# pcb_telemetria.net
KiCad netlist of a schematic drawn in EAGLE
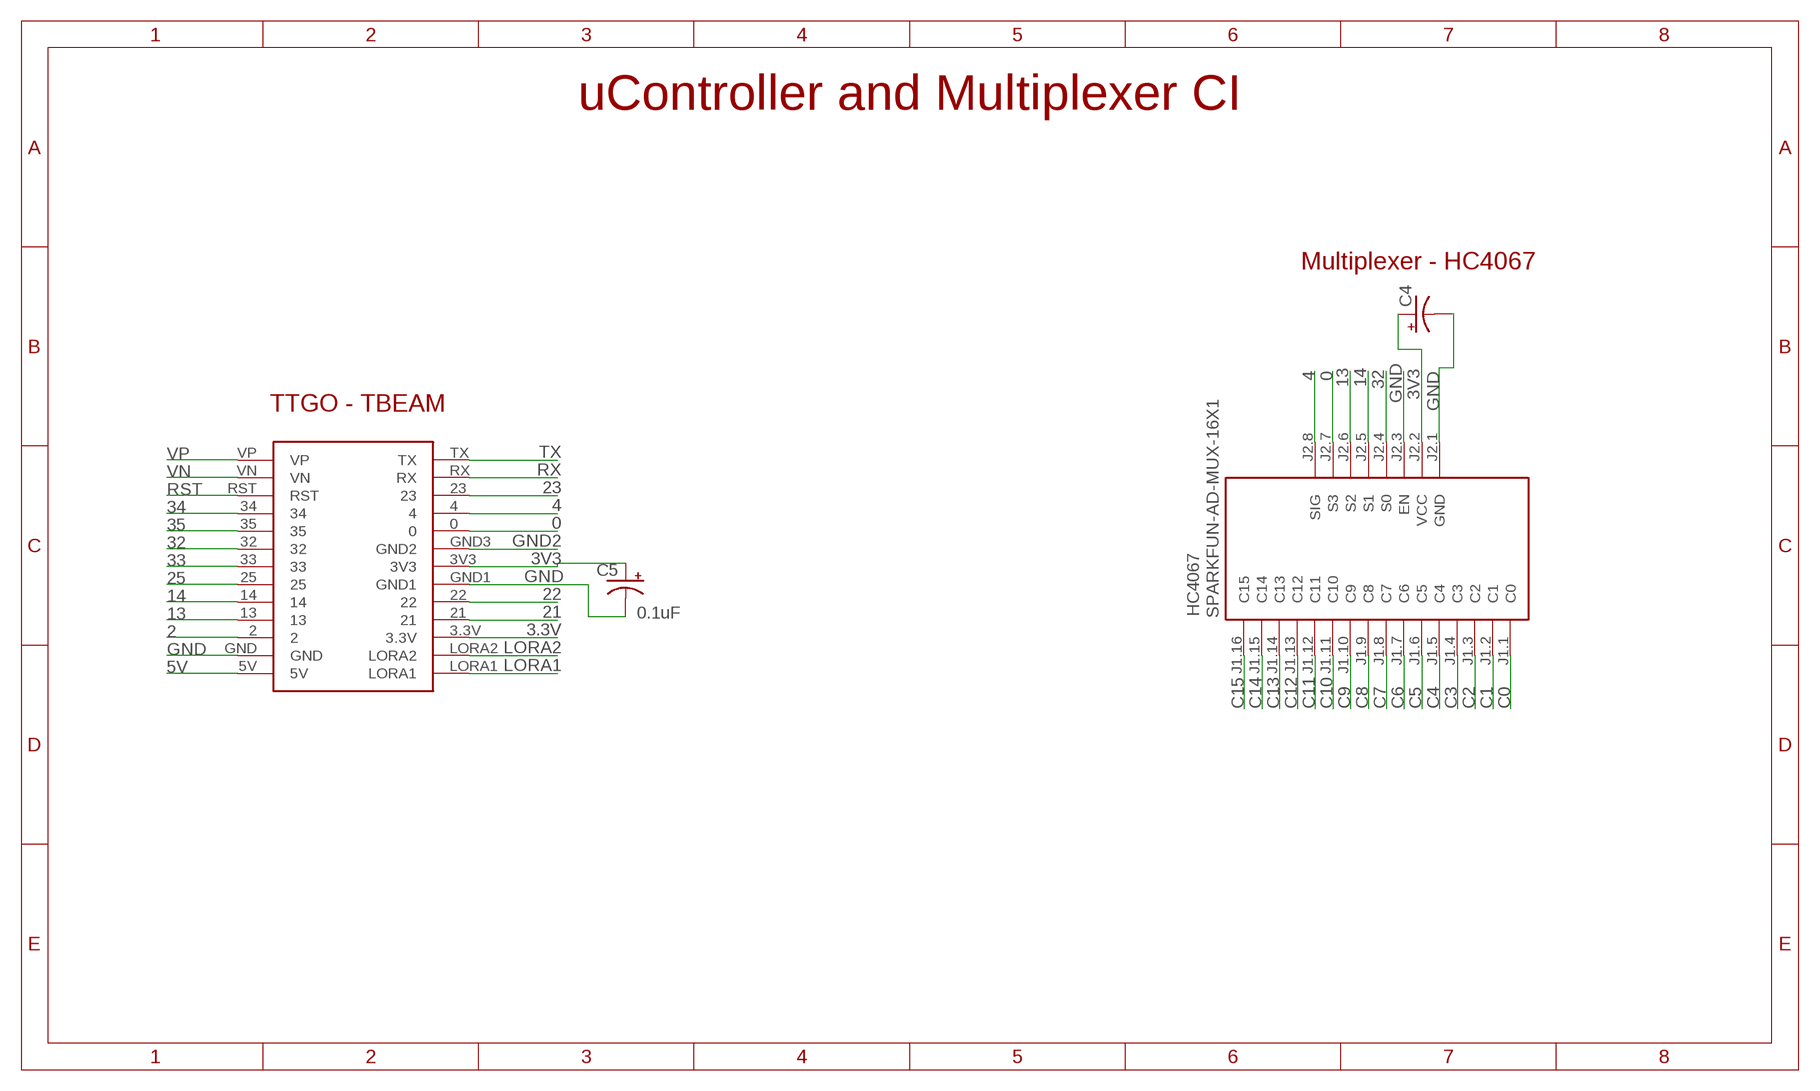
[diagram p0: schematic, sheet 1]
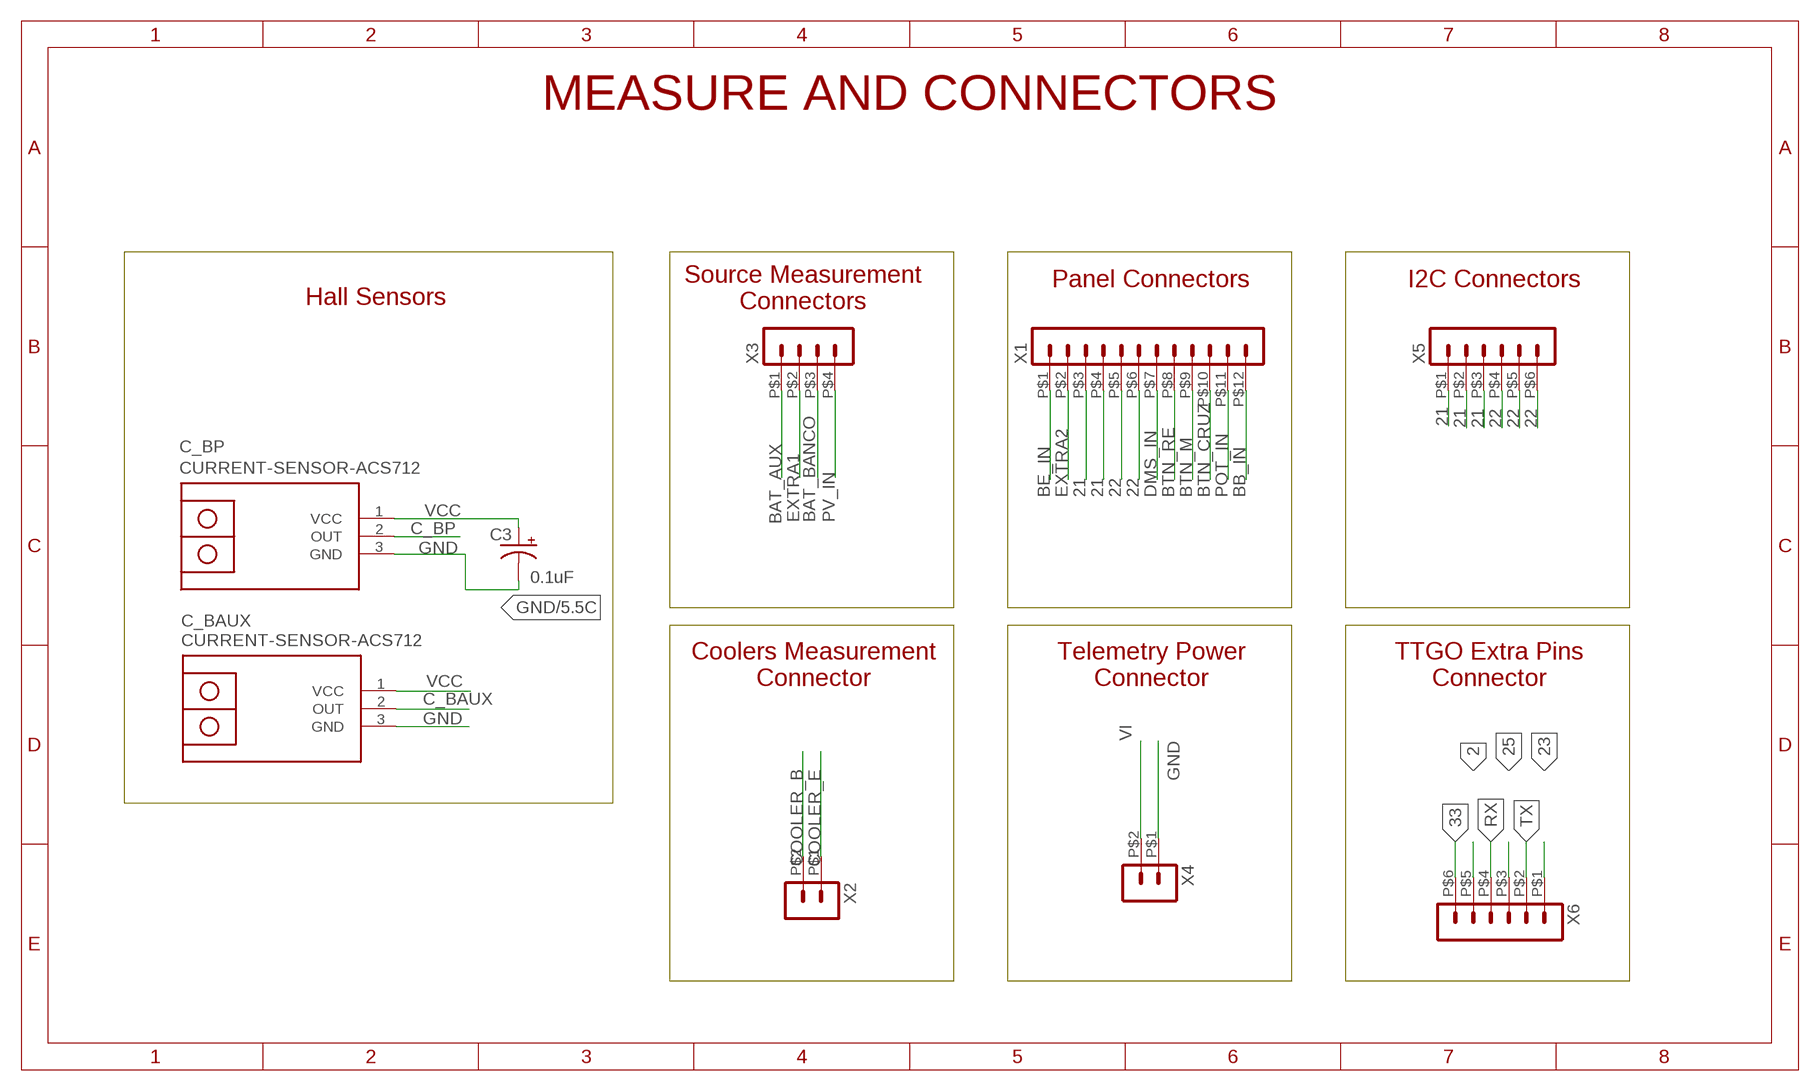
[diagram p1: schematic, sheet 2]
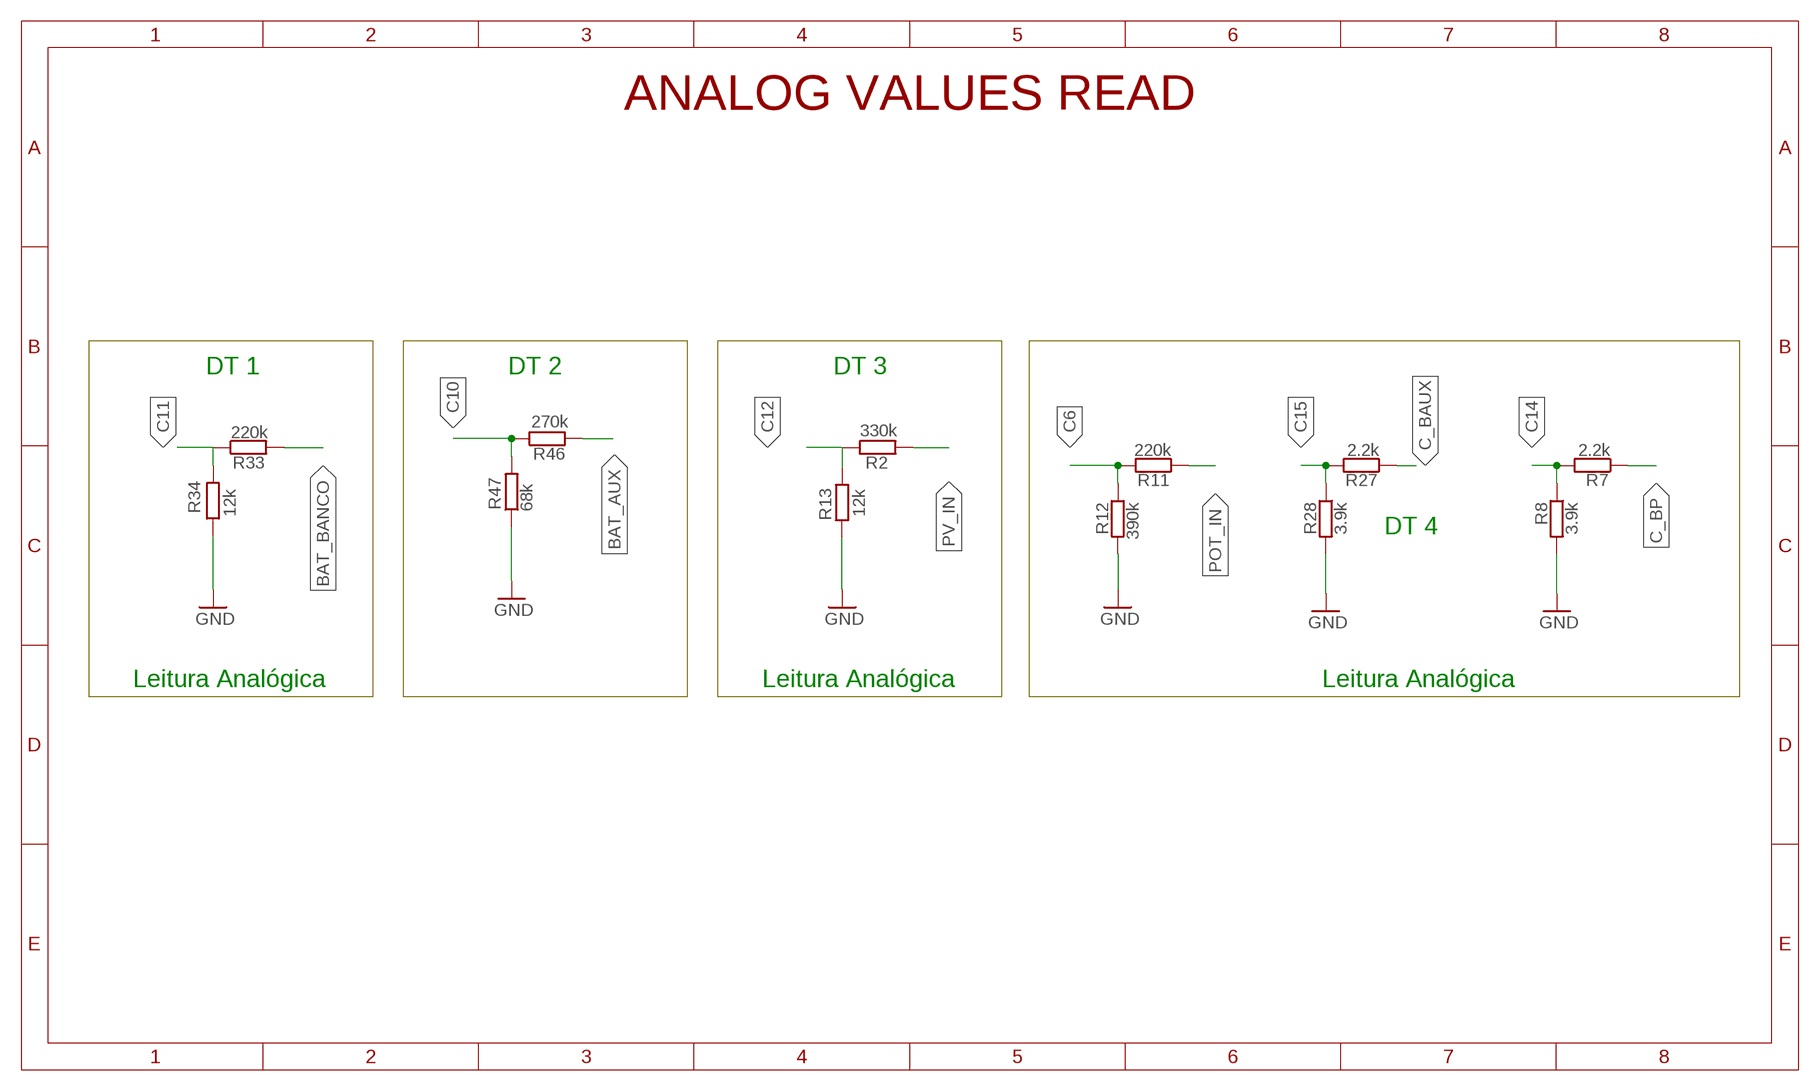
[diagram p2: schematic, sheet 3]
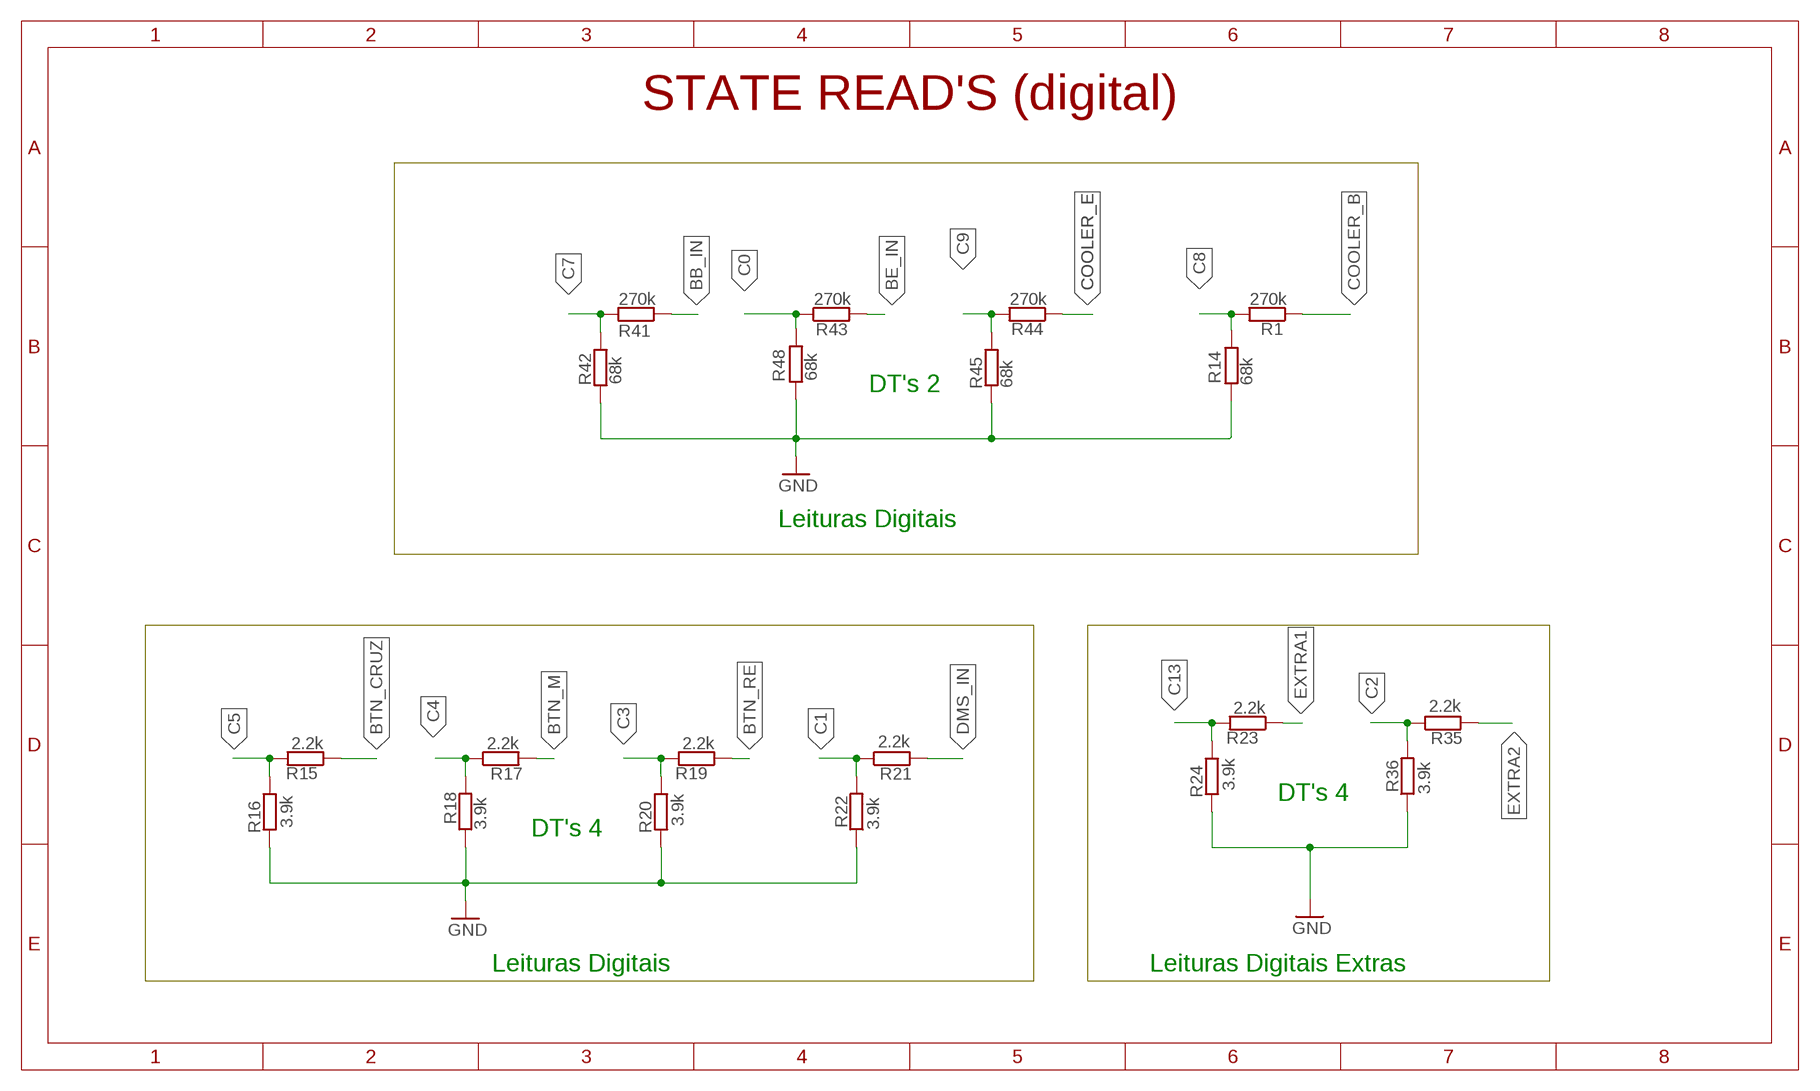
[diagram p3: schematic, sheet 4]
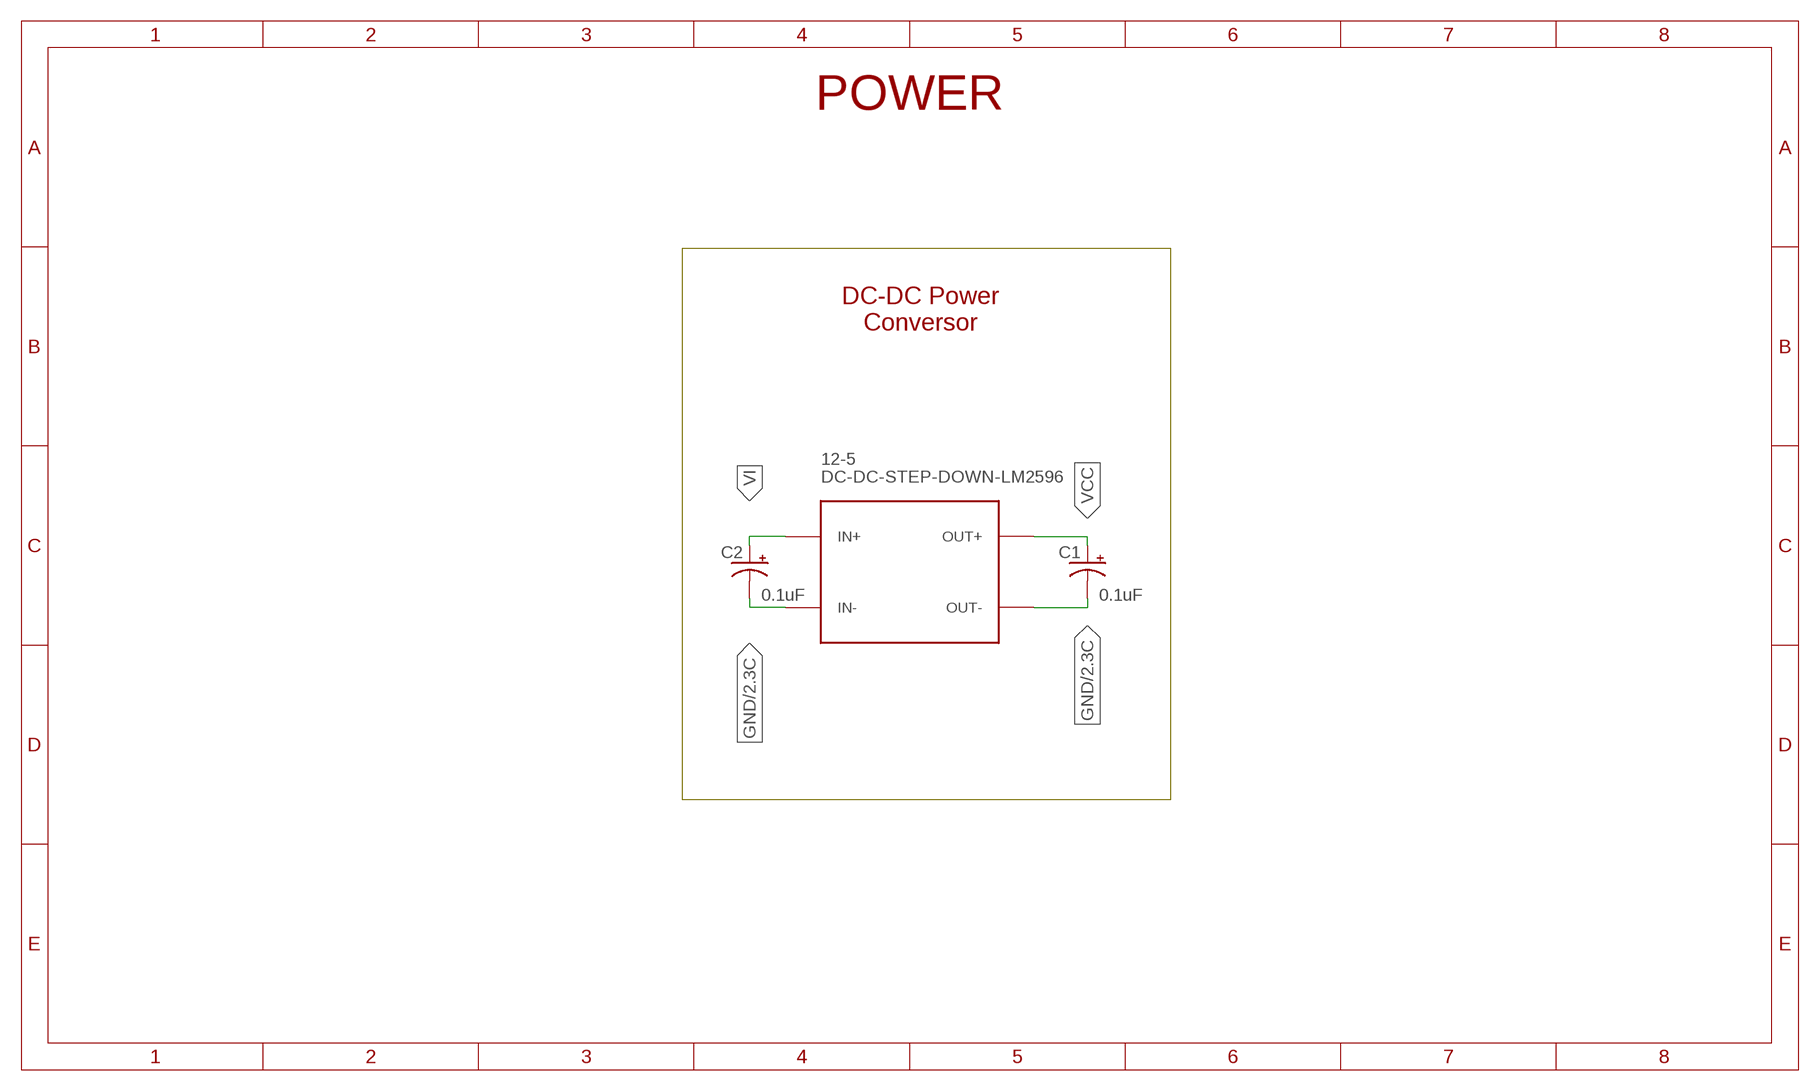
[diagram p4: schematic, sheet 5]

(export (version "E")
  (design (tool "Eeschema 10.0.6"))
  (components
    (comp (ref "C4")
      (value "CPOL-USE5-5")
      (footprint "eagle-import:E5-5")
      (libsource (lib "eagle-import") (part "CPOL-USE5-5"))
    )
    (comp (ref "C5")
      (value "0.1uF")
      (footprint "eagle-import:E5-5")
      (libsource (lib "eagle-import") (part "CPOL-USE5-5"))
    )
    (comp (ref "HC4067")
      (value "SPARKFUN-AD-MUX-16X1")
      (footprint "eagle-import:SPARKFUN-AD-MUX-16X1")
      (libsource (lib "eagle-import") (part "SPARKFUN-AD-MUX-16X1"))
    )
    (comp (ref "U$1")
      (value "TTGOBEAM")
      (footprint "eagle-import:TTGOBEAM")
      (libsource (lib "eagle-import") (part "TTGOBEAM"))
    )
    (comp (ref "R2")
      (value "330k")
      (footprint "eagle-import:0204_7")
      (libsource (lib "eagle-import") (part "R-EU_0204/7"))
    )
    (comp (ref "R7")
      (value "2.2k")
      (footprint "eagle-import:0204_7")
      (libsource (lib "eagle-import") (part "R-EU_0204/7"))
    )
    (comp (ref "R8")
      (value "3.9k")
      (footprint "eagle-import:0204_7")
      (libsource (lib "eagle-import") (part "R-EU_0204/7"))
    )
    (comp (ref "R11")
      (value "220k")
      (footprint "eagle-import:0204_7")
      (libsource (lib "eagle-import") (part "R-EU_0204/7"))
    )
    (comp (ref "R12")
      (value "390k")
      (footprint "eagle-import:0204_7")
      (libsource (lib "eagle-import") (part "R-EU_0204/7"))
    )
    (comp (ref "R13")
      (value "12k")
      (footprint "eagle-import:0204_7")
      (libsource (lib "eagle-import") (part "R-EU_0204/7"))
    )
    (comp (ref "R27")
      (value "2.2k")
      (footprint "eagle-import:0204_7")
      (libsource (lib "eagle-import") (part "R-EU_0204/7"))
    )
    (comp (ref "R28")
      (value "3.9k")
      (footprint "eagle-import:0204_7")
      (libsource (lib "eagle-import") (part "R-EU_0204/7"))
    )
    (comp (ref "R33")
      (value "220k")
      (footprint "eagle-import:0204_7")
      (libsource (lib "eagle-import") (part "R-EU_0204/7"))
    )
    (comp (ref "R34")
      (value "12k")
      (footprint "eagle-import:0204_7")
      (libsource (lib "eagle-import") (part "R-EU_0204/7"))
    )
    (comp (ref "R46")
      (value "270k")
      (footprint "eagle-import:0204_7")
      (libsource (lib "eagle-import") (part "R-EU_0204/7"))
    )
    (comp (ref "R47")
      (value "68k")
      (footprint "eagle-import:0204_7")
      (libsource (lib "eagle-import") (part "R-EU_0204/7"))
    )
    (comp (ref "12-5")
      (value "DC-DC-STEP-DOWN-LM2596")
      (footprint "eagle-import:DC-DC-STEP-DOWN-LM2596")
      (libsource (lib "eagle-import") (part "DC-DC-STEP-DOWN-LM2596"))
    )
    (comp (ref "C1")
      (value "0.1uF")
      (footprint "eagle-import:E5-5")
      (libsource (lib "eagle-import") (part "CPOL-USE5-5"))
    )
    (comp (ref "C2")
      (value "0.1uF")
      (footprint "eagle-import:E5-5")
      (libsource (lib "eagle-import") (part "CPOL-USE5-5"))
    )
    (comp (ref "C3")
      (value "0.1uF")
      (footprint "eagle-import:E5-5")
      (libsource (lib "eagle-import") (part "CPOL-USE5-5"))
    )
    (comp (ref "C_BAUX")
      (value "CURRENT-SENSOR-ACS712")
      (footprint "eagle-import:CURRENT-SENSOR-ACS712")
      (libsource (lib "eagle-import") (part "CURRENT-SENSOR-ACS712"))
    )
    (comp (ref "C_BP")
      (value "CURRENT-SENSOR-ACS712")
      (footprint "eagle-import:CURRENT-SENSOR-ACS712")
      (libsource (lib "eagle-import") (part "CURRENT-SENSOR-ACS712"))
    )
    (comp (ref "X1")
      (value "HEADER_POS12_43045-1212")
      (footprint "eagle-import:43045-1212")
      (libsource (lib "eagle-import") (part "HEADER_POS12_?43045-1212"))
    )
    (comp (ref "X2")
      (value "HEADER_POS2_43045-0212")
      (footprint "eagle-import:43045-0212")
      (libsource (lib "eagle-import") (part "HEADER_POS2_?43045-0212"))
    )
    (comp (ref "X3")
      (value "HEADER_POS4_43045-0412")
      (footprint "eagle-import:43045-0412")
      (libsource (lib "eagle-import") (part "HEADER_POS4_?43045-0412"))
    )
    (comp (ref "X4")
      (value "HEADER_POS2_43045-0212")
      (footprint "eagle-import:43045-0212")
      (libsource (lib "eagle-import") (part "HEADER_POS2_?43045-0212"))
    )
    (comp (ref "X5")
      (value "HEADER_POS6_43045-0612")
      (footprint "eagle-import:43045-0612")
      (libsource (lib "eagle-import") (part "HEADER_POS6_?43045-0612"))
    )
    (comp (ref "X6")
      (value "HEADER_POS6_43045-0612")
      (footprint "eagle-import:43045-0612")
      (libsource (lib "eagle-import") (part "HEADER_POS6_?43045-0612"))
    )
    (comp (ref "R1")
      (value "270k")
      (footprint "eagle-import:0204_7")
      (libsource (lib "eagle-import") (part "R-EU_0204/7"))
    )
    (comp (ref "R14")
      (value "68k")
      (footprint "eagle-import:0204_7")
      (libsource (lib "eagle-import") (part "R-EU_0204/7"))
    )
    (comp (ref "R15")
      (value "2.2k")
      (footprint "eagle-import:0204_7")
      (libsource (lib "eagle-import") (part "R-EU_0204/7"))
    )
    (comp (ref "R16")
      (value "3.9k")
      (footprint "eagle-import:0204_7")
      (libsource (lib "eagle-import") (part "R-EU_0204/7"))
    )
    (comp (ref "R17")
      (value "2.2k")
      (footprint "eagle-import:0204_7")
      (libsource (lib "eagle-import") (part "R-EU_0204/7"))
    )
    (comp (ref "R18")
      (value "3.9k")
      (footprint "eagle-import:0204_7")
      (libsource (lib "eagle-import") (part "R-EU_0204/7"))
    )
    (comp (ref "R19")
      (value "2.2k")
      (footprint "eagle-import:0204_7")
      (libsource (lib "eagle-import") (part "R-EU_0204/7"))
    )
    (comp (ref "R20")
      (value "3.9k")
      (footprint "eagle-import:0204_7")
      (libsource (lib "eagle-import") (part "R-EU_0204/7"))
    )
    (comp (ref "R21")
      (value "2.2k")
      (footprint "eagle-import:0204_7")
      (libsource (lib "eagle-import") (part "R-EU_0204/7"))
    )
    (comp (ref "R22")
      (value "3.9k")
      (footprint "eagle-import:0204_7")
      (libsource (lib "eagle-import") (part "R-EU_0204/7"))
    )
    (comp (ref "R23")
      (value "2.2k")
      (footprint "eagle-import:0204_7")
      (libsource (lib "eagle-import") (part "R-EU_0204/7"))
    )
    (comp (ref "R24")
      (value "3.9k")
      (footprint "eagle-import:0204_7")
      (libsource (lib "eagle-import") (part "R-EU_0204/7"))
    )
    (comp (ref "R35")
      (value "2.2k")
      (footprint "eagle-import:0204_7")
      (libsource (lib "eagle-import") (part "R-EU_0204/7"))
    )
    (comp (ref "R36")
      (value "3.9k")
      (footprint "eagle-import:0204_7")
      (libsource (lib "eagle-import") (part "R-EU_0204/7"))
    )
    (comp (ref "R41")
      (value "270k")
      (footprint "eagle-import:0204_7")
      (libsource (lib "eagle-import") (part "R-EU_0204/7"))
    )
    (comp (ref "R42")
      (value "68k")
      (footprint "eagle-import:0204_7")
      (libsource (lib "eagle-import") (part "R-EU_0204/7"))
    )
    (comp (ref "R43")
      (value "270k")
      (footprint "eagle-import:0204_7")
      (libsource (lib "eagle-import") (part "R-EU_0204/7"))
    )
    (comp (ref "R44")
      (value "270k")
      (footprint "eagle-import:0204_7")
      (libsource (lib "eagle-import") (part "R-EU_0204/7"))
    )
    (comp (ref "R45")
      (value "68k")
      (footprint "eagle-import:0204_7")
      (libsource (lib "eagle-import") (part "R-EU_0204/7"))
    )
    (comp (ref "R48")
      (value "68k")
      (footprint "eagle-import:0204_7")
      (libsource (lib "eagle-import") (part "R-EU_0204/7"))
    )
  )
  (nets
    (net (code "1") (name "0") (class "Default")
      (node (ref "HC4067") (pin "J2.7") (pinfunction "S3_J2.7") (pintype "bidirectional"))
      (node (ref "U$1") (pin "0") (pinfunction "0_0") (pintype "bidirectional"))
    )
    (net (code "2") (name "2") (class "Default")
      (node (ref "U$1") (pin "2") (pinfunction "2_2") (pintype "bidirectional"))
      (node (ref "X6") (pin "P$5") (pinfunction "5_P$5") (pintype "passive"))
    )
    (net (code "3") (name "3.3V") (class "Default")
      (node (ref "U$1") (pin "3.3V") (pinfunction "3.3V_3.3V") (pintype "bidirectional"))
    )
    (net (code "4") (name "3V3") (class "Default")
      (node (ref "C4") (pin "+") (pinfunction "+_+") (pintype "passive"))
      (node (ref "C5") (pin "+") (pinfunction "+_+") (pintype "passive"))
      (node (ref "HC4067") (pin "J2.2") (pinfunction "VCC_J2.2") (pintype "power_in"))
      (node (ref "U$1") (pin "3V3") (pinfunction "3V3_3V3") (pintype "bidirectional"))
    )
    (net (code "5") (name "4") (class "Default")
      (node (ref "HC4067") (pin "J2.8") (pinfunction "SIG_J2.8") (pintype "bidirectional"))
      (node (ref "U$1") (pin "4") (pinfunction "4_4") (pintype "bidirectional"))
    )
    (net (code "6") (name "5V") (class "Default")
      (node (ref "U$1") (pin "5V") (pinfunction "5V_5V") (pintype "bidirectional"))
    )
    (net (code "7") (name "13") (class "Default")
      (node (ref "HC4067") (pin "J2.6") (pinfunction "S2_J2.6") (pintype "bidirectional"))
      (node (ref "U$1") (pin "13") (pinfunction "13_13") (pintype "bidirectional"))
    )
    (net (code "8") (name "14") (class "Default")
      (node (ref "HC4067") (pin "J2.5") (pinfunction "S1_J2.5") (pintype "bidirectional"))
      (node (ref "U$1") (pin "14") (pinfunction "14_14") (pintype "bidirectional"))
    )
    (net (code "9") (name "21") (class "Default")
      (node (ref "U$1") (pin "21") (pinfunction "21_21") (pintype "bidirectional"))
      (node (ref "X1") (pin "P$3") (pinfunction "3_P$3") (pintype "passive"))
      (node (ref "X1") (pin "P$4") (pinfunction "4_P$4") (pintype "passive"))
      (node (ref "X5") (pin "P$1") (pinfunction "1_P$1") (pintype "passive"))
      (node (ref "X5") (pin "P$2") (pinfunction "2_P$2") (pintype "passive"))
      (node (ref "X5") (pin "P$3") (pinfunction "3_P$3") (pintype "passive"))
    )
    (net (code "10") (name "22") (class "Default")
      (node (ref "U$1") (pin "22") (pinfunction "22_22") (pintype "bidirectional"))
      (node (ref "X1") (pin "P$5") (pinfunction "5_P$5") (pintype "passive"))
      (node (ref "X1") (pin "P$6") (pinfunction "6_P$6") (pintype "passive"))
      (node (ref "X5") (pin "P$4") (pinfunction "4_P$4") (pintype "passive"))
      (node (ref "X5") (pin "P$5") (pinfunction "5_P$5") (pintype "passive"))
      (node (ref "X5") (pin "P$6") (pinfunction "6_P$6") (pintype "passive"))
    )
    (net (code "11") (name "23") (class "Default")
      (node (ref "U$1") (pin "23") (pinfunction "23_23") (pintype "bidirectional"))
      (node (ref "X6") (pin "P$1") (pinfunction "1_P$1") (pintype "passive"))
    )
    (net (code "12") (name "25") (class "Default")
      (node (ref "U$1") (pin "25") (pinfunction "25_25") (pintype "bidirectional"))
      (node (ref "X6") (pin "P$3") (pinfunction "3_P$3") (pintype "passive"))
    )
    (net (code "13") (name "32") (class "Default")
      (node (ref "HC4067") (pin "J2.4") (pinfunction "S0_J2.4") (pintype "bidirectional"))
      (node (ref "U$1") (pin "32") (pinfunction "32_32") (pintype "bidirectional"))
    )
    (net (code "14") (name "33") (class "Default")
      (node (ref "U$1") (pin "33") (pinfunction "33_33") (pintype "bidirectional"))
      (node (ref "X6") (pin "P$6") (pinfunction "6_P$6") (pintype "passive"))
    )
    (net (code "15") (name "34") (class "Default")
      (node (ref "U$1") (pin "34") (pinfunction "34_34") (pintype "bidirectional"))
    )
    (net (code "16") (name "35") (class "Default")
      (node (ref "U$1") (pin "35") (pinfunction "35_35") (pintype "bidirectional"))
    )
    (net (code "17") (name "BAT_AUX") (class "Default")
      (node (ref "R46") (pin "2") (pinfunction "2_2") (pintype "passive"))
      (node (ref "X3") (pin "P$1") (pinfunction "1_P$1") (pintype "passive"))
    )
    (net (code "18") (name "BAT_BANCO") (class "Default")
      (node (ref "R33") (pin "2") (pinfunction "2_2") (pintype "passive"))
      (node (ref "X3") (pin "P$3") (pinfunction "3_P$3") (pintype "passive"))
    )
    (net (code "19") (name "BB_IN") (class "Default")
      (node (ref "R41") (pin "1") (pinfunction "1_1") (pintype "passive"))
      (node (ref "X1") (pin "P$12") (pinfunction "12_P$12") (pintype "passive"))
    )
    (net (code "20") (name "BE_IN") (class "Default")
      (node (ref "R43") (pin "2") (pinfunction "2_2") (pintype "passive"))
      (node (ref "X1") (pin "P$1") (pinfunction "1_P$1") (pintype "passive"))
    )
    (net (code "21") (name "BTN_CRUZ") (class "Default")
      (node (ref "R15") (pin "1") (pinfunction "1_1") (pintype "passive"))
      (node (ref "X1") (pin "P$10") (pinfunction "10_P$10") (pintype "passive"))
    )
    (net (code "22") (name "BTN_M") (class "Default")
      (node (ref "R17") (pin "2") (pinfunction "2_2") (pintype "passive"))
      (node (ref "X1") (pin "P$9") (pinfunction "9_P$9") (pintype "passive"))
    )
    (net (code "23") (name "BTN_RE") (class "Default")
      (node (ref "R19") (pin "1") (pinfunction "1_1") (pintype "passive"))
      (node (ref "X1") (pin "P$8") (pinfunction "8_P$8") (pintype "passive"))
    )
    (net (code "24") (name "C0") (class "Default")
      (node (ref "HC4067") (pin "J1.1") (pinfunction "C0_J1.1") (pintype "bidirectional"))
      (node (ref "R43") (pin "1") (pinfunction "1_1") (pintype "passive"))
      (node (ref "R48") (pin "1") (pinfunction "1_1") (pintype "passive"))
    )
    (net (code "25") (name "C1") (class "Default")
      (node (ref "HC4067") (pin "J1.2") (pinfunction "C1_J1.2") (pintype "bidirectional"))
      (node (ref "R21") (pin "1") (pinfunction "1_1") (pintype "passive"))
      (node (ref "R22") (pin "2") (pinfunction "2_2") (pintype "passive"))
    )
    (net (code "26") (name "C2") (class "Default")
      (node (ref "HC4067") (pin "J1.3") (pinfunction "C2_J1.3") (pintype "bidirectional"))
      (node (ref "R35") (pin "1") (pinfunction "1_1") (pintype "passive"))
      (node (ref "R36") (pin "2") (pinfunction "2_2") (pintype "passive"))
    )
    (net (code "27") (name "C3") (class "Default")
      (node (ref "HC4067") (pin "J1.4") (pinfunction "C3_J1.4") (pintype "bidirectional"))
      (node (ref "R19") (pin "2") (pinfunction "2_2") (pintype "passive"))
      (node (ref "R20") (pin "1") (pinfunction "1_1") (pintype "passive"))
    )
    (net (code "28") (name "C4") (class "Default")
      (node (ref "HC4067") (pin "J1.5") (pinfunction "C4_J1.5") (pintype "bidirectional"))
      (node (ref "R17") (pin "1") (pinfunction "1_1") (pintype "passive"))
      (node (ref "R18") (pin "2") (pinfunction "2_2") (pintype "passive"))
    )
    (net (code "29") (name "C5") (class "Default")
      (node (ref "HC4067") (pin "J1.6") (pinfunction "C5_J1.6") (pintype "bidirectional"))
      (node (ref "R15") (pin "2") (pinfunction "2_2") (pintype "passive"))
      (node (ref "R16") (pin "1") (pinfunction "1_1") (pintype "passive"))
    )
    (net (code "30") (name "C6") (class "Default")
      (node (ref "HC4067") (pin "J1.7") (pinfunction "C6_J1.7") (pintype "bidirectional"))
      (node (ref "R11") (pin "2") (pinfunction "2_2") (pintype "passive"))
      (node (ref "R12") (pin "1") (pinfunction "1_1") (pintype "passive"))
    )
    (net (code "31") (name "C7") (class "Default")
      (node (ref "HC4067") (pin "J1.8") (pinfunction "C7_J1.8") (pintype "bidirectional"))
      (node (ref "R41") (pin "2") (pinfunction "2_2") (pintype "passive"))
      (node (ref "R42") (pin "1") (pinfunction "1_1") (pintype "passive"))
    )
    (net (code "32") (name "C8") (class "Default")
      (node (ref "HC4067") (pin "J1.9") (pinfunction "C8_J1.9") (pintype "bidirectional"))
      (node (ref "R1") (pin "2") (pinfunction "2_2") (pintype "passive"))
      (node (ref "R14") (pin "2") (pinfunction "2_2") (pintype "passive"))
    )
    (net (code "33") (name "C9") (class "Default")
      (node (ref "HC4067") (pin "J1.10") (pinfunction "C9_J1.10") (pintype "bidirectional"))
      (node (ref "R44") (pin "2") (pinfunction "2_2") (pintype "passive"))
      (node (ref "R45") (pin "1") (pinfunction "1_1") (pintype "passive"))
    )
    (net (code "34") (name "C10") (class "Default")
      (node (ref "HC4067") (pin "J1.11") (pinfunction "C10_J1.11") (pintype "bidirectional"))
      (node (ref "R46") (pin "1") (pinfunction "1_1") (pintype "passive"))
      (node (ref "R47") (pin "2") (pinfunction "2_2") (pintype "passive"))
    )
    (net (code "35") (name "C11") (class "Default")
      (node (ref "HC4067") (pin "J1.12") (pinfunction "C11_J1.12") (pintype "bidirectional"))
      (node (ref "R33") (pin "1") (pinfunction "1_1") (pintype "passive"))
      (node (ref "R34") (pin "2") (pinfunction "2_2") (pintype "passive"))
    )
    (net (code "36") (name "C12") (class "Default")
      (node (ref "HC4067") (pin "J1.13") (pinfunction "C12_J1.13") (pintype "bidirectional"))
      (node (ref "R13") (pin "2") (pinfunction "2_2") (pintype "passive"))
      (node (ref "R2") (pin "1") (pinfunction "1_1") (pintype "passive"))
    )
    (net (code "37") (name "C13") (class "Default")
      (node (ref "HC4067") (pin "J1.14") (pinfunction "C13_J1.14") (pintype "bidirectional"))
      (node (ref "R23") (pin "2") (pinfunction "2_2") (pintype "passive"))
      (node (ref "R24") (pin "1") (pinfunction "1_1") (pintype "passive"))
    )
    (net (code "38") (name "C14") (class "Default")
      (node (ref "HC4067") (pin "J1.15") (pinfunction "C14_J1.15") (pintype "bidirectional"))
      (node (ref "R7") (pin "2") (pinfunction "2_2") (pintype "passive"))
      (node (ref "R8") (pin "1") (pinfunction "1_1") (pintype "passive"))
    )
    (net (code "39") (name "C15") (class "Default")
      (node (ref "HC4067") (pin "J1.16") (pinfunction "C15_J1.16") (pintype "bidirectional"))
      (node (ref "R27") (pin "2") (pinfunction "2_2") (pintype "passive"))
      (node (ref "R28") (pin "1") (pinfunction "1_1") (pintype "passive"))
    )
    (net (code "40") (name "COOLER_B") (class "Default")
      (node (ref "R1") (pin "1") (pinfunction "1_1") (pintype "passive"))
      (node (ref "X2") (pin "P$2") (pinfunction "2_P$2") (pintype "passive"))
    )
    (net (code "41") (name "COOLER_E") (class "Default")
      (node (ref "R44") (pin "1") (pinfunction "1_1") (pintype "passive"))
      (node (ref "X2") (pin "P$1") (pinfunction "1_P$1") (pintype "passive"))
    )
    (net (code "42") (name "C_BAUX") (class "Default")
      (node (ref "C_BAUX") (pin "2") (pinfunction "OUT_2") (pintype "output"))
      (node (ref "R27") (pin "1") (pinfunction "1_1") (pintype "passive"))
    )
    (net (code "43") (name "C_BP") (class "Default")
      (node (ref "C_BP") (pin "2") (pinfunction "OUT_2") (pintype "output"))
      (node (ref "R7") (pin "1") (pinfunction "1_1") (pintype "passive"))
    )
    (net (code "44") (name "DMS_IN") (class "Default")
      (node (ref "R21") (pin "2") (pinfunction "2_2") (pintype "passive"))
      (node (ref "X1") (pin "P$7") (pinfunction "7_P$7") (pintype "passive"))
    )
    (net (code "45") (name "EXTRA1") (class "Default")
      (node (ref "R23") (pin "1") (pinfunction "1_1") (pintype "passive"))
      (node (ref "X3") (pin "P$2") (pinfunction "2_P$2") (pintype "passive"))
    )
    (net (code "46") (name "EXTRA2") (class "Default")
      (node (ref "R35") (pin "2") (pinfunction "2_2") (pintype "passive"))
      (node (ref "X1") (pin "P$2") (pinfunction "2_P$2") (pintype "passive"))
    )
    (net (code "47") (name "GND") (class "Default")
      (node (ref "12-5") (pin "IN-") (pinfunction "IN-_IN-") (pintype "bidirectional"))
      (node (ref "12-5") (pin "OUT-") (pinfunction "OUT-_OUT-") (pintype "bidirectional"))
      (node (ref "C1") (pin "-") (pinfunction "-_-") (pintype "passive"))
      (node (ref "C2") (pin "-") (pinfunction "-_-") (pintype "passive"))
      (node (ref "C3") (pin "-") (pinfunction "-_-") (pintype "passive"))
      (node (ref "C4") (pin "-") (pinfunction "-_-") (pintype "passive"))
      (node (ref "C5") (pin "-") (pinfunction "-_-") (pintype "passive"))
      (node (ref "C_BAUX") (pin "3") (pinfunction "GND_3") (pintype "power_in"))
      (node (ref "C_BP") (pin "3") (pinfunction "GND_3") (pintype "power_in"))
      (node (ref "HC4067") (pin "J2.1") (pinfunction "GND_J2.1") (pintype "power_in"))
      (node (ref "HC4067") (pin "J2.3") (pinfunction "EN_J2.3") (pintype "input"))
      (node (ref "R12") (pin "2") (pinfunction "2_2") (pintype "passive"))
      (node (ref "R13") (pin "1") (pinfunction "1_1") (pintype "passive"))
      (node (ref "R14") (pin "1") (pinfunction "1_1") (pintype "passive"))
      (node (ref "R16") (pin "2") (pinfunction "2_2") (pintype "passive"))
      (node (ref "R18") (pin "1") (pinfunction "1_1") (pintype "passive"))
      (node (ref "R20") (pin "2") (pinfunction "2_2") (pintype "passive"))
      (node (ref "R22") (pin "1") (pinfunction "1_1") (pintype "passive"))
      (node (ref "R24") (pin "2") (pinfunction "2_2") (pintype "passive"))
      (node (ref "R28") (pin "2") (pinfunction "2_2") (pintype "passive"))
      (node (ref "R34") (pin "1") (pinfunction "1_1") (pintype "passive"))
      (node (ref "R36") (pin "1") (pinfunction "1_1") (pintype "passive"))
      (node (ref "R42") (pin "2") (pinfunction "2_2") (pintype "passive"))
      (node (ref "R45") (pin "2") (pinfunction "2_2") (pintype "passive"))
      (node (ref "R47") (pin "1") (pinfunction "1_1") (pintype "passive"))
      (node (ref "R48") (pin "2") (pinfunction "2_2") (pintype "passive"))
      (node (ref "R8") (pin "2") (pinfunction "2_2") (pintype "passive"))
      (node (ref "U$1") (pin "GND") (pinfunction "GND_GND") (pintype "bidirectional"))
      (node (ref "U$1") (pin "GND1") (pinfunction "GND1_GND1") (pintype "bidirectional"))
      (node (ref "X4") (pin "P$1") (pinfunction "1_P$1") (pintype "passive"))
    )
    (net (code "48") (name "GND2") (class "Default")
      (node (ref "U$1") (pin "GND3") (pinfunction "GND2_GND3") (pintype "bidirectional"))
    )
    (net (code "49") (name "LORA1") (class "Default")
      (node (ref "U$1") (pin "LORA1") (pinfunction "LORA1_LORA1") (pintype "bidirectional"))
    )
    (net (code "50") (name "LORA2") (class "Default")
      (node (ref "U$1") (pin "LORA2") (pinfunction "LORA2_LORA2") (pintype "bidirectional"))
    )
    (net (code "51") (name "POT_IN") (class "Default")
      (node (ref "R11") (pin "1") (pinfunction "1_1") (pintype "passive"))
      (node (ref "X1") (pin "P$11") (pinfunction "11_P$11") (pintype "passive"))
    )
    (net (code "52") (name "PV_IN") (class "Default")
      (node (ref "R2") (pin "2") (pinfunction "2_2") (pintype "passive"))
      (node (ref "X3") (pin "P$4") (pinfunction "4_P$4") (pintype "passive"))
    )
    (net (code "53") (name "RST") (class "Default")
      (node (ref "U$1") (pin "RST") (pinfunction "RST_RST") (pintype "bidirectional"))
    )
    (net (code "54") (name "RX") (class "Default")
      (node (ref "U$1") (pin "RX") (pinfunction "RX_RX") (pintype "bidirectional"))
      (node (ref "X6") (pin "P$4") (pinfunction "4_P$4") (pintype "passive"))
    )
    (net (code "55") (name "TX") (class "Default")
      (node (ref "U$1") (pin "TX") (pinfunction "TX_TX") (pintype "bidirectional"))
      (node (ref "X6") (pin "P$2") (pinfunction "2_P$2") (pintype "passive"))
    )
    (net (code "56") (name "VCC") (class "Default")
      (node (ref "12-5") (pin "OUT+") (pinfunction "OUT+_OUT+") (pintype "bidirectional"))
      (node (ref "C1") (pin "+") (pinfunction "+_+") (pintype "passive"))
      (node (ref "C3") (pin "+") (pinfunction "+_+") (pintype "passive"))
      (node (ref "C_BAUX") (pin "1") (pinfunction "VCC_1") (pintype "power_in"))
      (node (ref "C_BP") (pin "1") (pinfunction "VCC_1") (pintype "power_in"))
    )
    (net (code "57") (name "VI") (class "Default")
      (node (ref "12-5") (pin "IN+") (pinfunction "IN+_IN+") (pintype "bidirectional"))
      (node (ref "C2") (pin "+") (pinfunction "+_+") (pintype "passive"))
      (node (ref "X4") (pin "P$2") (pinfunction "2_P$2") (pintype "passive"))
    )
    (net (code "58") (name "VN") (class "Default")
      (node (ref "U$1") (pin "VN") (pinfunction "VN_VN") (pintype "bidirectional"))
    )
    (net (code "59") (name "VP") (class "Default")
      (node (ref "U$1") (pin "VP") (pinfunction "VP_VP") (pintype "bidirectional"))
    )
  )
)
